# SCH_Signal_Jammer_2023-12-11.net
KiCad netlist of a schematic drawn in EasyEDA
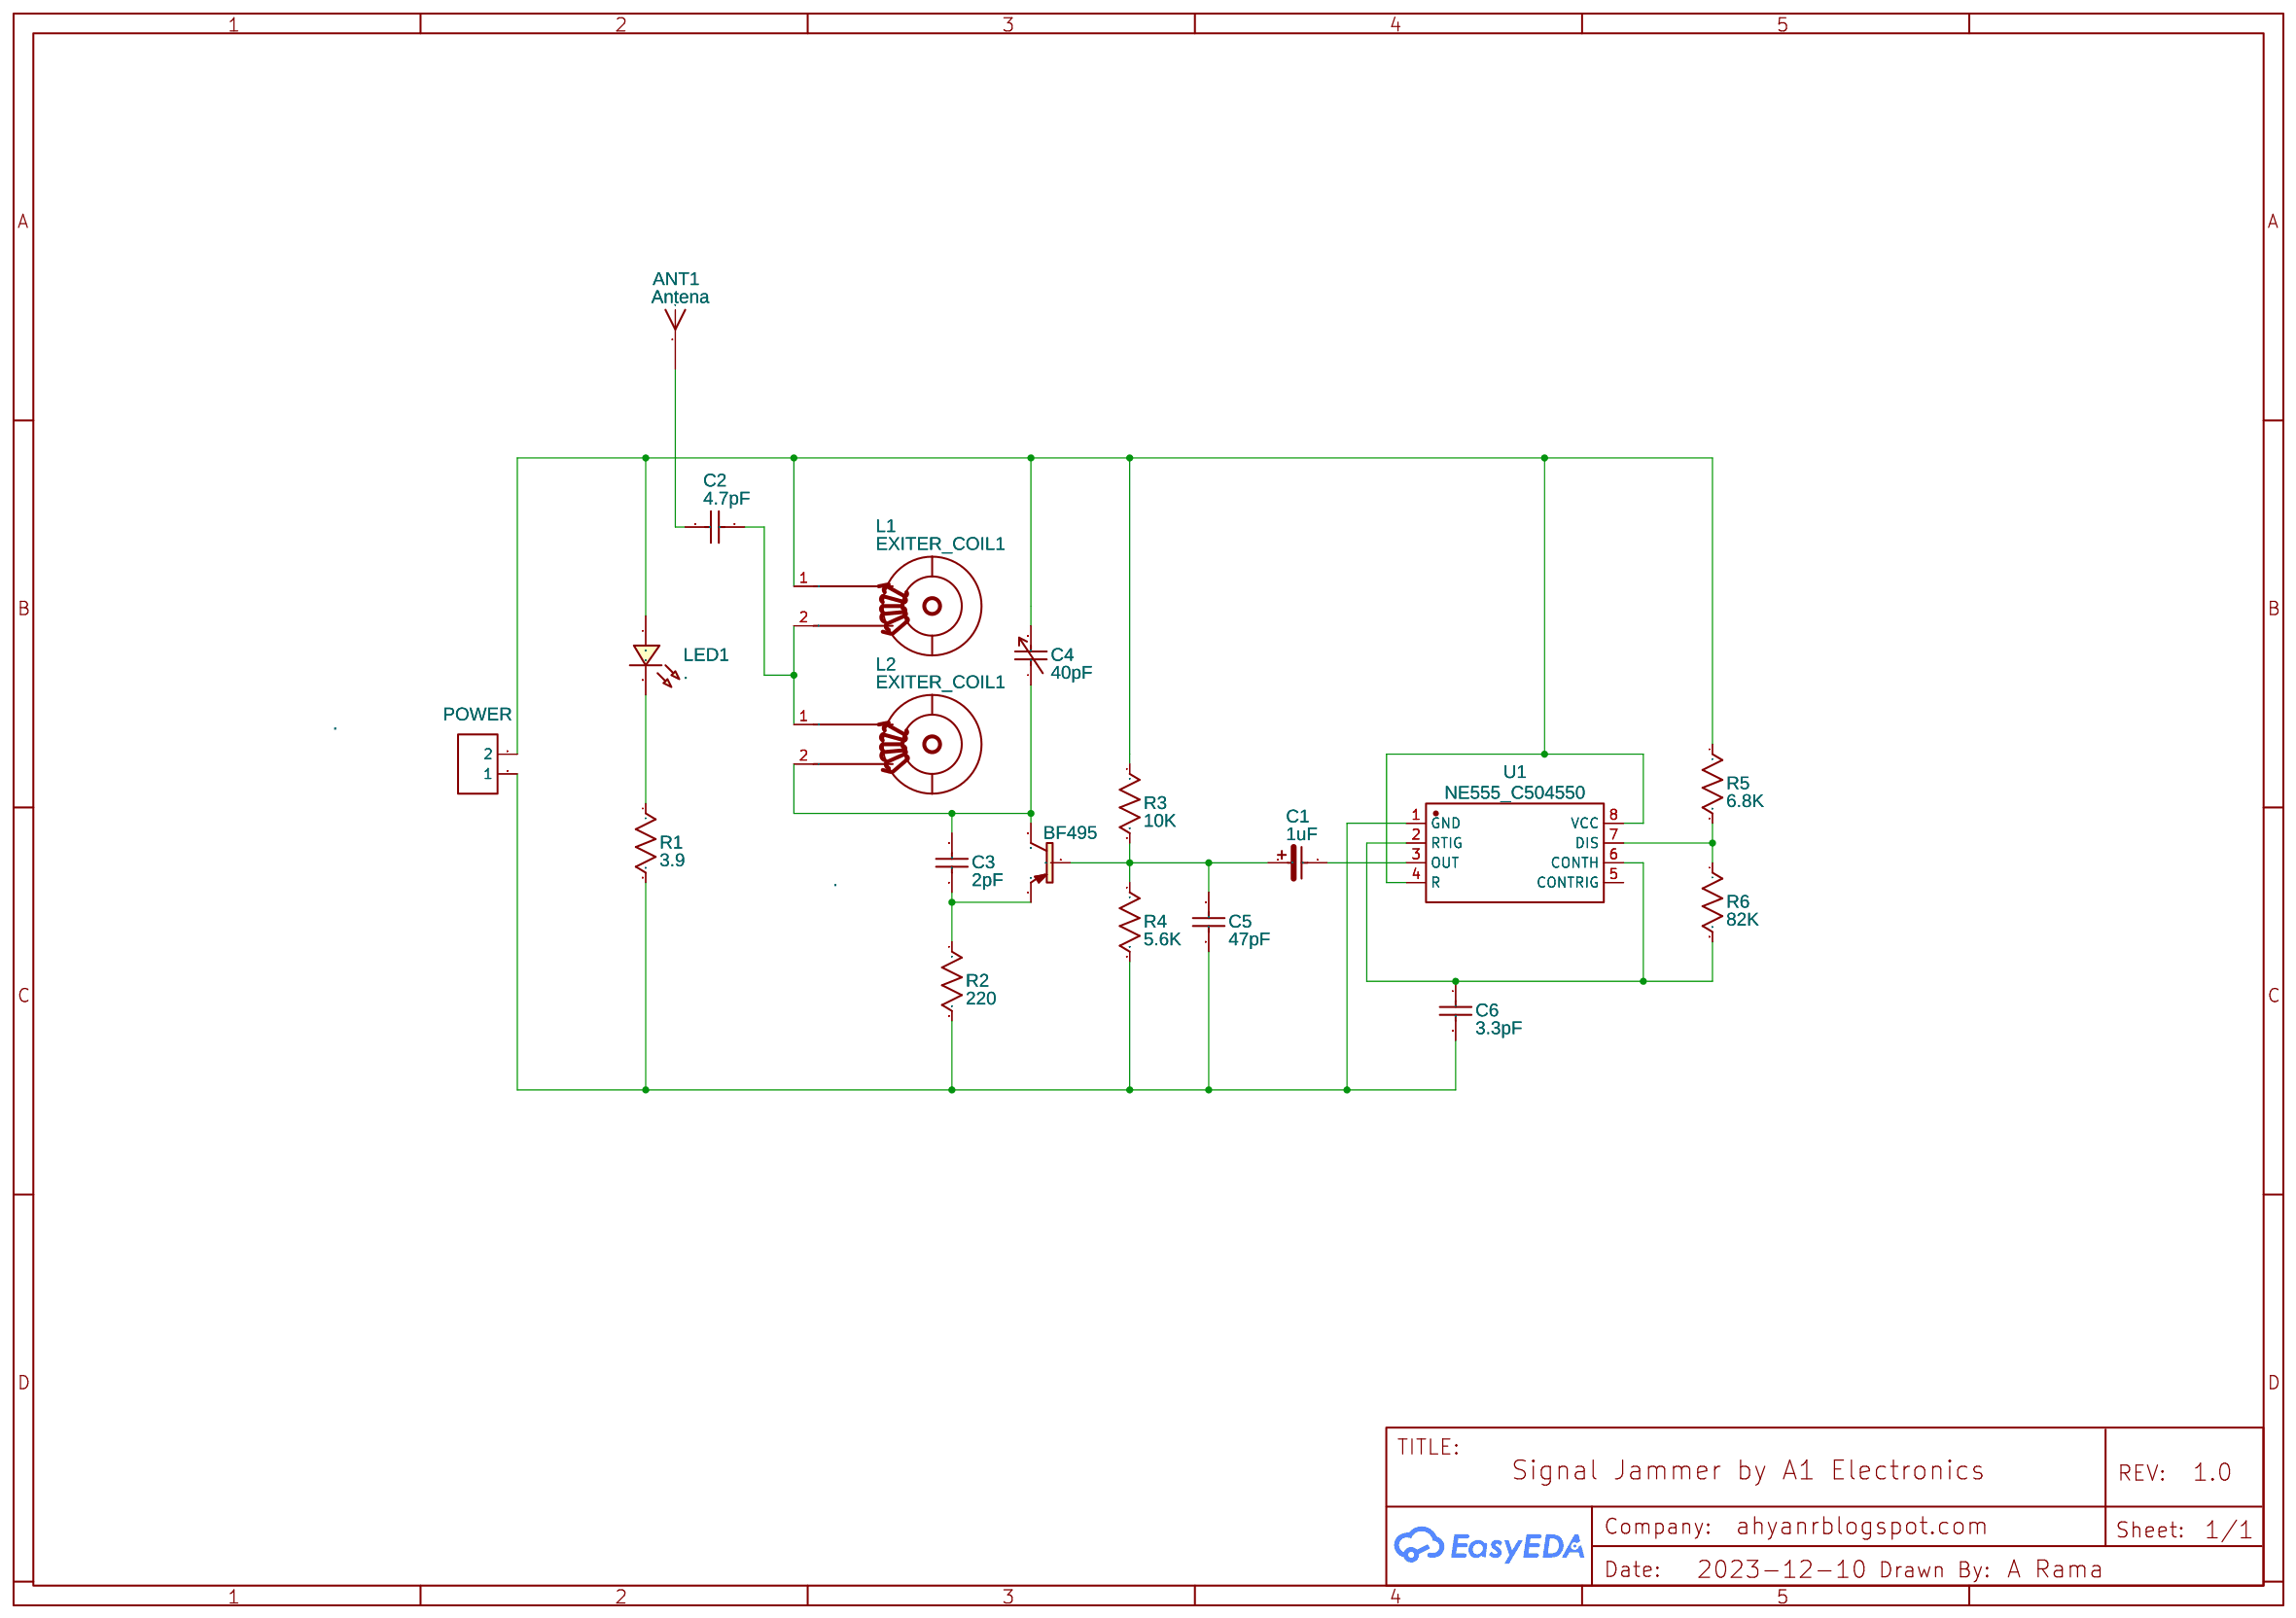
[diagram p0: schematic sheet]

(export (version "E")
  (design (tool "Eeschema 10.0.6"))
  (components
    (comp (ref "ANT1") (value "Antena") (libsource (lib "") (part "Antena")))
    (comp (ref "BF495") (value ".") (libsource (lib "") (part "BF495-PNP-TO92-CEB")))
    (comp (ref "C1")
      (value "1uF")
      (fields (field (name "Manufacturer Part") "TAP105K050SCS") (field (name "Manufacturer") "AVX"))
      (libsource (lib "") (part "1uF"))
    )
    (comp (ref "C2")
      (value "4.7pF")
      (fields
        (field (name "Manufacturer Part") "Calibration capacitor4.7nf 5% 100V")
        (field (name "Manufacturer") "ReliaPro")
      )
      (libsource (lib "") (part "Ceramic Disc Capacitor_1"))
    )
    (comp (ref "C3")
      (value "2pF")
      (fields
        (field (name "Manufacturer Part") "Calibration capacitor4.7nf 5% 100V")
        (field (name "Manufacturer") "ReliaPro")
      )
      (libsource (lib "") (part "Ceramic Disc Capacitor"))
    )
    (comp (ref "C4")
      (value "40pF")
      (fields (field (name "Manufacturer Part") "JML06-1-70P") (field (name "Manufacturer") "JML"))
      (libsource (lib "") (part "JML06-1-70P"))
    )
    (comp (ref "C5")
      (value "47pF")
      (fields
        (field (name "Manufacturer Part") "Calibration capacitor4.7nf 5% 100V")
        (field (name "Manufacturer") "ReliaPro")
      )
      (libsource (lib "") (part "Ceramic Disc Capacitor"))
    )
    (comp (ref "C6")
      (value "3.3pF")
      (fields
        (field (name "Manufacturer Part") "Calibration capacitor4.7nf 5% 100V")
        (field (name "Manufacturer") "ReliaPro")
      )
      (libsource (lib "") (part "Ceramic Disc Capacitor"))
    )
    (comp (ref "L1") (value "EXITER_COIL1") (libsource (lib "") (part "EXITER_COIL1 COPY")))
    (comp (ref "L2") (value "EXITER_COIL1") (libsource (lib "") (part "EXITER_COIL1 COPY")))
    (comp (ref "LED1")
      (value ".")
      (fields
        (field (name "Manufacturer Part") "333-2SURD/S530-A3")
        (field (name "Manufacturer") "EVERLIGHT(台湾亿光)")
      )
      (libsource (lib "") (part "LED-TH-5mm_R"))
    )
    (comp (ref "POWER") (value ".") (libsource (lib "") (part "CONN-TH_2P-P5.00")))
    (comp (ref "R1") (value "3.9") (libsource (lib "") (part "R_AXIAL-0.4_US")))
    (comp (ref "R2") (value "220") (libsource (lib "") (part "R_AXIAL-0.4_US")))
    (comp (ref "R3") (value "10K") (libsource (lib "") (part "R_AXIAL-0.4_US")))
    (comp (ref "R4") (value "5.6K") (libsource (lib "") (part "R_AXIAL-0.4_US")))
    (comp (ref "R5") (value "6.8K") (libsource (lib "") (part "R_AXIAL-0.4_US")))
    (comp (ref "R6") (value "82K") (libsource (lib "") (part "R_AXIAL-0.4_US")))
    (comp (ref "U1")
      (value "NE555_C504550")
      (fields (field (name "Manufacturer Part") "NE555") (field (name "Manufacturer") "Gcore(上海国芯)"))
      (libsource (lib "") (part "NE555_C504550"))
    )
  )
  (nets
    (net (code "1") (name "Net-(ANT1-Pad1)") (class "Default")
      (node (ref "ANT1") (pin "1") (pinfunction "1_1") (pintype "unspecified"))
      (node (ref "C2") (pin "1") (pinfunction "1_1") (pintype "input"))
    )
    (net (code "2") (name "Net-(BF495-PadB)") (class "Default")
      (node (ref "BF495") (pin "B") (pinfunction "B_B") (pintype "unspecified"))
      (node (ref "C1") (pin "1") (pinfunction "1_1") (pintype "input"))
      (node (ref "C5") (pin "1") (pinfunction "1_1") (pintype "input"))
      (node (ref "R3") (pin "2") (pinfunction "2_2") (pintype "unspecified"))
      (node (ref "R4") (pin "1") (pinfunction "1_1") (pintype "unspecified"))
    )
    (net (code "3") (name "Net-(BF495-PadE)") (class "Default")
      (node (ref "BF495") (pin "E") (pinfunction "E_E") (pintype "unspecified"))
      (node (ref "C3") (pin "2") (pinfunction "2_2") (pintype "input"))
      (node (ref "R2") (pin "1") (pinfunction "1_1") (pintype "unspecified"))
    )
    (net (code "4") (name "Net-(L1-C)") (class "Default")
      (node (ref "C4") (pin "2") (pinfunction "2_2") (pintype "input"))
      (node (ref "L1") (pin "1") (pinfunction "C_1") (pintype "unspecified"))
      (node (ref "LED1") (pin "1") (pinfunction "1_1") (pintype "unspecified"))
      (node (ref "POWER") (pin "2") (pinfunction "2_2") (pintype "unspecified"))
      (node (ref "R3") (pin "1") (pinfunction "1_1") (pintype "unspecified"))
      (node (ref "R5") (pin "1") (pinfunction "1_1") (pintype "unspecified"))
      (node (ref "U1") (pin "4") (pinfunction "R_4") (pintype "unspecified"))
      (node (ref "U1") (pin "8") (pinfunction "VCC_8") (pintype "unspecified"))
    )
    (net (code "5") (name "Net-(L1-E)") (class "Default")
      (node (ref "C2") (pin "2") (pinfunction "2_2") (pintype "input"))
      (node (ref "L1") (pin "2") (pinfunction "E_2") (pintype "unspecified"))
      (node (ref "L2") (pin "1") (pinfunction "C_1") (pintype "unspecified"))
    )
    (net (code "6") (name "Net-(L2-E)") (class "Default")
      (node (ref "BF495") (pin "C") (pinfunction "C_C") (pintype "unspecified"))
      (node (ref "C3") (pin "1") (pinfunction "1_1") (pintype "input"))
      (node (ref "C4") (pin "1") (pinfunction "1_1") (pintype "input"))
      (node (ref "L2") (pin "2") (pinfunction "E_2") (pintype "unspecified"))
    )
    (net (code "7") (name "Net-(LED1-Pad2)") (class "Default")
      (node (ref "LED1") (pin "2") (pinfunction "2_2") (pintype "unspecified"))
      (node (ref "R1") (pin "1") (pinfunction "1_1") (pintype "unspecified"))
    )
    (net (code "8") (name "Net-(U1-CONTH)") (class "Default")
      (node (ref "C6") (pin "1") (pinfunction "1_1") (pintype "input"))
      (node (ref "R6") (pin "2") (pinfunction "2_2") (pintype "unspecified"))
      (node (ref "U1") (pin "2") (pinfunction "RTIG_2") (pintype "unspecified"))
      (node (ref "U1") (pin "6") (pinfunction "CONTH_6") (pintype "unspecified"))
    )
    (net (code "9") (name "Net-(U1-DIS)") (class "Default")
      (node (ref "R5") (pin "2") (pinfunction "2_2") (pintype "unspecified"))
      (node (ref "R6") (pin "1") (pinfunction "1_1") (pintype "unspecified"))
      (node (ref "U1") (pin "7") (pinfunction "DIS_7") (pintype "unspecified"))
    )
    (net (code "10") (name "Net-(U1-GND)") (class "Default")
      (node (ref "C5") (pin "2") (pinfunction "2_2") (pintype "input"))
      (node (ref "C6") (pin "2") (pinfunction "2_2") (pintype "input"))
      (node (ref "POWER") (pin "1") (pinfunction "1_1") (pintype "unspecified"))
      (node (ref "R1") (pin "2") (pinfunction "2_2") (pintype "unspecified"))
      (node (ref "R2") (pin "2") (pinfunction "2_2") (pintype "unspecified"))
      (node (ref "R4") (pin "2") (pinfunction "2_2") (pintype "unspecified"))
      (node (ref "U1") (pin "1") (pinfunction "GND_1") (pintype "unspecified"))
    )
    (net (code "11") (name "Net-(U1-OUT)") (class "Default")
      (node (ref "C1") (pin "2") (pinfunction "2_2") (pintype "input"))
      (node (ref "U1") (pin "3") (pinfunction "OUT_3") (pintype "unspecified"))
    )
    (net (code "12") (name "unconnected-(U1-CONTRIG-Pad5)") (class "Default")
      (node (ref "U1") (pin "5") (pinfunction "CONTRIG_5") (pintype "unspecified"))
    )
  )
)
